# SCH_mechakey_2023-10-28.net
KiCad netlist of a schematic drawn in EasyEDA
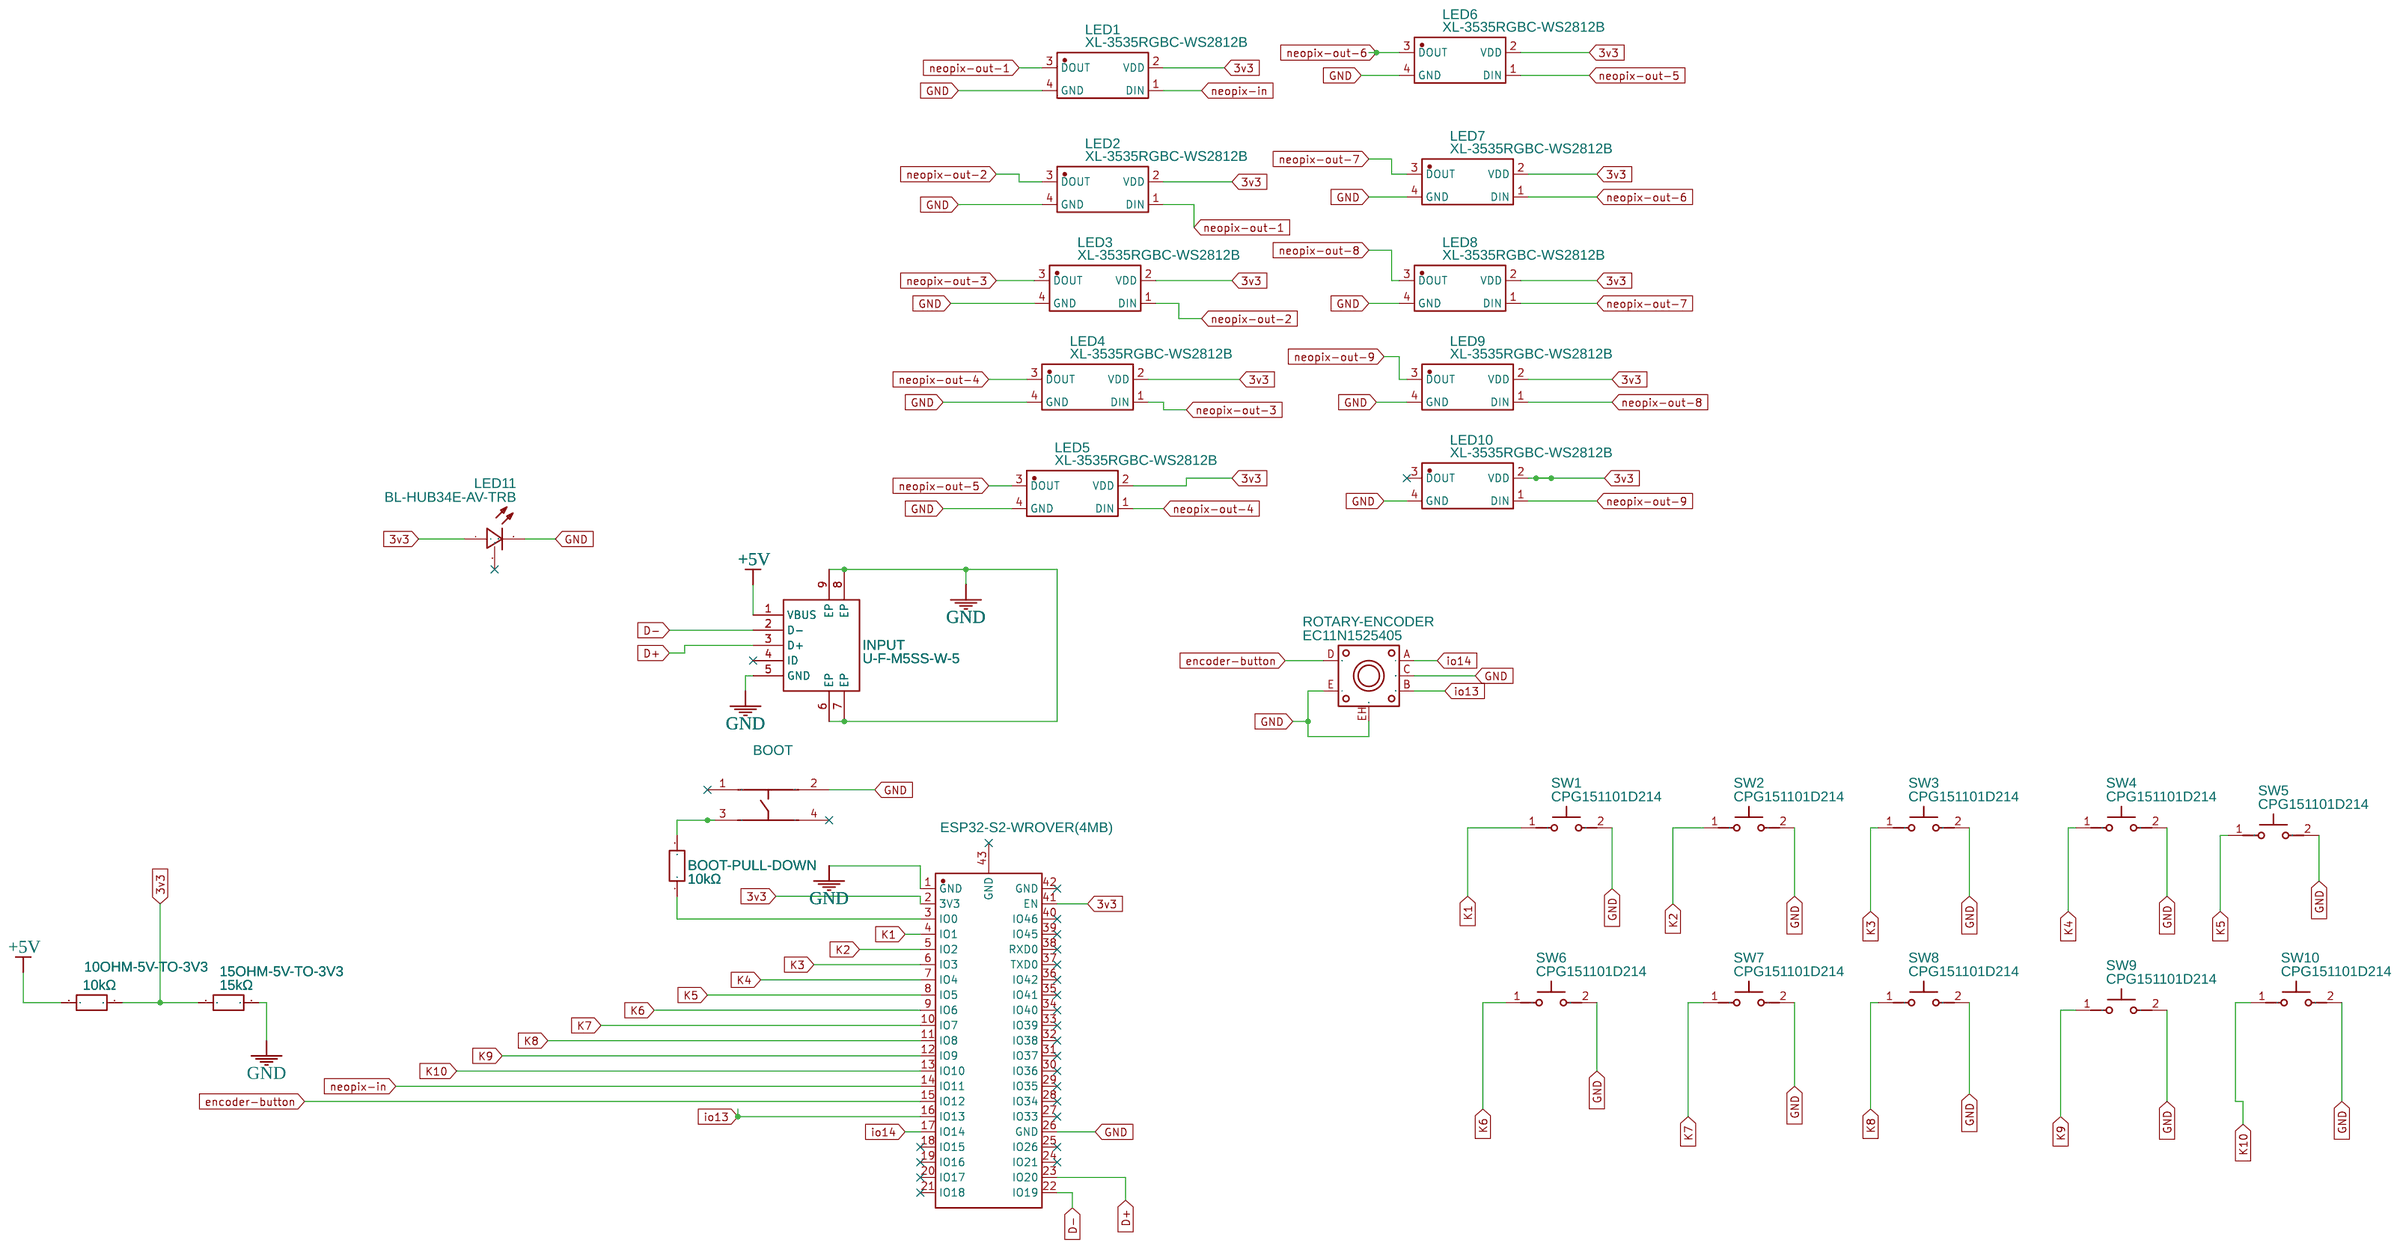
[diagram p0: schematic sheet]

(export (version "E")
  (design (tool "Eeschema 10.0.6"))
  (components
    (comp (ref "10OHM-5V-TO-3V3")
      (value "10kΩ")
      (fields (field (name "Manufacturer") "PANASONIC(松下)"))
      (libsource (lib "") (part "ERJUP3F1002V_1"))
    )
    (comp (ref "15OHM-5V-TO-3V3")
      (value "15kΩ")
      (fields (field (name "Manufacturer") "VO(翔胜)"))
      (libsource (lib "") (part "CR1/8W-15K±5%-OT26"))
    )
    (comp (ref "BOOT")
      (value "PTS810SJM250SMTRLFS")
      (fields (field (name "Manufacturer") "C&K"))
      (libsource (lib "") (part "PTS810SJM250SMTRLFS"))
    )
    (comp (ref "BOOT-PULL-DOWN")
      (value "10kΩ")
      (fields (field (name "Manufacturer") "PANASONIC(松下)"))
      (libsource (lib "") (part "ERJUP3F1002V"))
    )
    (comp (ref "INPUT")
      (value "U-F-M5SS-W-5")
      (fields (field (name "Manufacturer") "韩国韩荣"))
      (libsource (lib "") (part "U-F-M5SS-W-5"))
    )
    (comp (ref "LED1")
      (value "XL-3535RGBC-WS2812B")
      (fields (field (name "Manufacturer") "XINGLIGHT(成兴光)"))
      (libsource (lib "") (part "XL-3535RGBC-WS2812B"))
    )
    (comp (ref "LED2")
      (value "XL-3535RGBC-WS2812B")
      (fields (field (name "Manufacturer") "XINGLIGHT(成兴光)"))
      (libsource (lib "") (part "XL-3535RGBC-WS2812B"))
    )
    (comp (ref "LED3")
      (value "XL-3535RGBC-WS2812B")
      (fields (field (name "Manufacturer") "XINGLIGHT(成兴光)"))
      (libsource (lib "") (part "XL-3535RGBC-WS2812B"))
    )
    (comp (ref "LED4")
      (value "XL-3535RGBC-WS2812B")
      (fields (field (name "Manufacturer") "XINGLIGHT(成兴光)"))
      (libsource (lib "") (part "XL-3535RGBC-WS2812B"))
    )
    (comp (ref "LED5")
      (value "XL-3535RGBC-WS2812B")
      (fields (field (name "Manufacturer") "XINGLIGHT(成兴光)"))
      (libsource (lib "") (part "XL-3535RGBC-WS2812B"))
    )
    (comp (ref "LED6")
      (value "XL-3535RGBC-WS2812B")
      (fields (field (name "Manufacturer") "XINGLIGHT(成兴光)"))
      (libsource (lib "") (part "XL-3535RGBC-WS2812B"))
    )
    (comp (ref "LED7")
      (value "XL-3535RGBC-WS2812B")
      (fields (field (name "Manufacturer") "XINGLIGHT(成兴光)"))
      (libsource (lib "") (part "XL-3535RGBC-WS2812B"))
    )
    (comp (ref "LED8")
      (value "XL-3535RGBC-WS2812B")
      (fields (field (name "Manufacturer") "XINGLIGHT(成兴光)"))
      (libsource (lib "") (part "XL-3535RGBC-WS2812B"))
    )
    (comp (ref "LED9")
      (value "XL-3535RGBC-WS2812B")
      (fields (field (name "Manufacturer") "XINGLIGHT(成兴光)"))
      (libsource (lib "") (part "XL-3535RGBC-WS2812B"))
    )
    (comp (ref "LED10")
      (value "XL-3535RGBC-WS2812B")
      (fields (field (name "Manufacturer") "XINGLIGHT(成兴光)"))
      (libsource (lib "") (part "XL-3535RGBC-WS2812B"))
    )
    (comp (ref "LED11")
      (value "BL-HUB34E-AV-TRB")
      (fields (field (name "Manufacturer") "BrtLed(佰鸿)"))
      (libsource (lib "") (part "BL-HUB34E-AV-TRB"))
    )
    (comp (ref "ROTARY-ENCODER")
      (value "EC11N1525405")
      (fields (field (name "Manufacturer") "ALPSALPINE(阿尔卑斯阿尔派)"))
      (libsource (lib "") (part "EC11N1525405"))
    )
    (comp (ref "SW1")
      (value "CPG151101D214")
      (fields (field (name "Manufacturer") "Kailh"))
      (libsource (lib "") (part "CPG151101D214"))
    )
    (comp (ref "SW2")
      (value "CPG151101D214")
      (fields (field (name "Manufacturer") "Kailh"))
      (libsource (lib "") (part "CPG151101D214"))
    )
    (comp (ref "SW3")
      (value "CPG151101D214")
      (fields (field (name "Manufacturer") "Kailh"))
      (libsource (lib "") (part "CPG151101D214"))
    )
    (comp (ref "SW4")
      (value "CPG151101D214")
      (fields (field (name "Manufacturer") "Kailh"))
      (libsource (lib "") (part "CPG151101D214"))
    )
    (comp (ref "SW5")
      (value "CPG151101D214")
      (fields (field (name "Manufacturer") "Kailh"))
      (libsource (lib "") (part "CPG151101D214"))
    )
    (comp (ref "SW6")
      (value "CPG151101D214")
      (fields (field (name "Manufacturer") "Kailh"))
      (libsource (lib "") (part "CPG151101D214"))
    )
    (comp (ref "SW7")
      (value "CPG151101D214")
      (fields (field (name "Manufacturer") "Kailh"))
      (libsource (lib "") (part "CPG151101D214"))
    )
    (comp (ref "SW8")
      (value "CPG151101D214")
      (fields (field (name "Manufacturer") "Kailh"))
      (libsource (lib "") (part "CPG151101D214"))
    )
    (comp (ref "SW9")
      (value "CPG151101D214")
      (fields (field (name "Manufacturer") "Kailh"))
      (libsource (lib "") (part "CPG151101D214"))
    )
    (comp (ref "SW10")
      (value "CPG151101D214")
      (fields (field (name "Manufacturer") "Kailh"))
      (libsource (lib "") (part "CPG151101D214"))
    )
    (comp (ref "U1")
      (value "ESP32-S2-WROVER(4MB)")
      (fields (field (name "Manufacturer") "ESPRESSIF(乐鑫)"))
      (libsource (lib "") (part "ESP32-S2-WROVER(4MB)"))
    )
  )
  (nets
    (net (code "1") (name "+5V") (class "Default")
      (node (ref "10OHM-5V-TO-3V3") (pin "1") (pinfunction "1_1") (pintype "unspecified"))
      (node (ref "INPUT") (pin "1") (pinfunction "VBUS_1") (pintype "unspecified"))
    )
    (net (code "2") (name "3v3") (class "Default")
      (node (ref "10OHM-5V-TO-3V3") (pin "2") (pinfunction "2_2") (pintype "unspecified"))
      (node (ref "15OHM-5V-TO-3V3") (pin "1") (pinfunction "1_1") (pintype "unspecified"))
      (node (ref "LED1") (pin "2") (pinfunction "VDD_2") (pintype "unspecified"))
      (node (ref "LED10") (pin "2") (pinfunction "VDD_2") (pintype "unspecified"))
      (node (ref "LED11") (pin "1") (pinfunction "A_1") (pintype "unspecified"))
      (node (ref "LED2") (pin "2") (pinfunction "VDD_2") (pintype "unspecified"))
      (node (ref "LED3") (pin "2") (pinfunction "VDD_2") (pintype "unspecified"))
      (node (ref "LED4") (pin "2") (pinfunction "VDD_2") (pintype "unspecified"))
      (node (ref "LED5") (pin "2") (pinfunction "VDD_2") (pintype "unspecified"))
      (node (ref "LED6") (pin "2") (pinfunction "VDD_2") (pintype "unspecified"))
      (node (ref "LED7") (pin "2") (pinfunction "VDD_2") (pintype "unspecified"))
      (node (ref "LED8") (pin "2") (pinfunction "VDD_2") (pintype "unspecified"))
      (node (ref "LED9") (pin "2") (pinfunction "VDD_2") (pintype "unspecified"))
      (node (ref "U1") (pin "2") (pinfunction "3V3_2") (pintype "unspecified"))
      (node (ref "U1") (pin "41") (pinfunction "EN_41") (pintype "unspecified"))
    )
    (net (code "3") (name "D+") (class "Default")
      (node (ref "INPUT") (pin "3") (pinfunction "D+_3") (pintype "unspecified"))
      (node (ref "U1") (pin "23") (pinfunction "IO20_23") (pintype "unspecified"))
    )
    (net (code "4") (name "D-") (class "Default")
      (node (ref "INPUT") (pin "2") (pinfunction "D-_2") (pintype "unspecified"))
      (node (ref "U1") (pin "22") (pinfunction "IO19_22") (pintype "unspecified"))
    )
    (net (code "5") (name "GND") (class "Default")
      (node (ref "15OHM-5V-TO-3V3") (pin "2") (pinfunction "2_2") (pintype "unspecified"))
      (node (ref "BOOT") (pin "2") (pinfunction "2_2") (pintype "unspecified"))
      (node (ref "INPUT") (pin "5") (pinfunction "GND_5") (pintype "unspecified"))
      (node (ref "INPUT") (pin "6") (pinfunction "EP_6") (pintype "unspecified"))
      (node (ref "INPUT") (pin "7") (pinfunction "EP_7") (pintype "unspecified"))
      (node (ref "INPUT") (pin "8") (pinfunction "EP_8") (pintype "unspecified"))
      (node (ref "INPUT") (pin "9") (pinfunction "EP_9") (pintype "unspecified"))
      (node (ref "LED1") (pin "4") (pinfunction "GND_4") (pintype "unspecified"))
      (node (ref "LED10") (pin "4") (pinfunction "GND_4") (pintype "unspecified"))
      (node (ref "LED11") (pin "2") (pinfunction "C_2") (pintype "unspecified"))
      (node (ref "LED2") (pin "4") (pinfunction "GND_4") (pintype "unspecified"))
      (node (ref "LED3") (pin "4") (pinfunction "GND_4") (pintype "unspecified"))
      (node (ref "LED4") (pin "4") (pinfunction "GND_4") (pintype "unspecified"))
      (node (ref "LED5") (pin "4") (pinfunction "GND_4") (pintype "unspecified"))
      (node (ref "LED6") (pin "4") (pinfunction "GND_4") (pintype "unspecified"))
      (node (ref "LED7") (pin "4") (pinfunction "GND_4") (pintype "unspecified"))
      (node (ref "LED8") (pin "4") (pinfunction "GND_4") (pintype "unspecified"))
      (node (ref "LED9") (pin "4") (pinfunction "GND_4") (pintype "unspecified"))
      (node (ref "ROTARY-ENCODER") (pin "C") (pinfunction "C_C") (pintype "unspecified"))
      (node (ref "ROTARY-ENCODER") (pin "E") (pinfunction "E_E") (pintype "unspecified"))
      (node (ref "ROTARY-ENCODER") (pin "EH") (pinfunction "EH_EH") (pintype "unspecified"))
      (node (ref "SW1") (pin "2") (pinfunction "2_2") (pintype "unspecified"))
      (node (ref "SW10") (pin "2") (pinfunction "2_2") (pintype "unspecified"))
      (node (ref "SW2") (pin "2") (pinfunction "2_2") (pintype "unspecified"))
      (node (ref "SW3") (pin "2") (pinfunction "2_2") (pintype "unspecified"))
      (node (ref "SW4") (pin "2") (pinfunction "2_2") (pintype "unspecified"))
      (node (ref "SW5") (pin "2") (pinfunction "2_2") (pintype "unspecified"))
      (node (ref "SW6") (pin "2") (pinfunction "2_2") (pintype "unspecified"))
      (node (ref "SW7") (pin "2") (pinfunction "2_2") (pintype "unspecified"))
      (node (ref "SW8") (pin "2") (pinfunction "2_2") (pintype "unspecified"))
      (node (ref "SW9") (pin "2") (pinfunction "2_2") (pintype "unspecified"))
      (node (ref "U1") (pin "1") (pinfunction "GND_1") (pintype "unspecified"))
      (node (ref "U1") (pin "26") (pinfunction "GND_26") (pintype "unspecified"))
    )
    (net (code "6") (name "K1") (class "Default")
      (node (ref "SW1") (pin "1") (pinfunction "1_1") (pintype "unspecified"))
      (node (ref "U1") (pin "4") (pinfunction "IO1_4") (pintype "unspecified"))
    )
    (net (code "7") (name "K2") (class "Default")
      (node (ref "SW2") (pin "1") (pinfunction "1_1") (pintype "unspecified"))
      (node (ref "U1") (pin "5") (pinfunction "IO2_5") (pintype "unspecified"))
    )
    (net (code "8") (name "K3") (class "Default")
      (node (ref "SW3") (pin "1") (pinfunction "1_1") (pintype "unspecified"))
      (node (ref "U1") (pin "6") (pinfunction "IO3_6") (pintype "unspecified"))
    )
    (net (code "9") (name "K4") (class "Default")
      (node (ref "SW4") (pin "1") (pinfunction "1_1") (pintype "unspecified"))
      (node (ref "U1") (pin "7") (pinfunction "IO4_7") (pintype "unspecified"))
    )
    (net (code "10") (name "K5") (class "Default")
      (node (ref "SW5") (pin "1") (pinfunction "1_1") (pintype "unspecified"))
      (node (ref "U1") (pin "8") (pinfunction "IO5_8") (pintype "unspecified"))
    )
    (net (code "11") (name "K6") (class "Default")
      (node (ref "SW6") (pin "1") (pinfunction "1_1") (pintype "unspecified"))
      (node (ref "U1") (pin "9") (pinfunction "IO6_9") (pintype "unspecified"))
    )
    (net (code "12") (name "K7") (class "Default")
      (node (ref "SW7") (pin "1") (pinfunction "1_1") (pintype "unspecified"))
      (node (ref "U1") (pin "10") (pinfunction "IO7_10") (pintype "unspecified"))
    )
    (net (code "13") (name "K8") (class "Default")
      (node (ref "SW8") (pin "1") (pinfunction "1_1") (pintype "unspecified"))
      (node (ref "U1") (pin "11") (pinfunction "IO8_11") (pintype "unspecified"))
    )
    (net (code "14") (name "K9") (class "Default")
      (node (ref "SW9") (pin "1") (pinfunction "1_1") (pintype "unspecified"))
      (node (ref "U1") (pin "12") (pinfunction "IO9_12") (pintype "unspecified"))
    )
    (net (code "15") (name "K10") (class "Default")
      (node (ref "SW10") (pin "1") (pinfunction "1_1") (pintype "unspecified"))
      (node (ref "U1") (pin "13") (pinfunction "IO10_13") (pintype "unspecified"))
    )
    (net (code "16") (name "Net-(BOOT-PULL-DOWN-Pad2)") (class "Default")
      (node (ref "BOOT") (pin "3") (pinfunction "3_3") (pintype "unspecified"))
      (node (ref "BOOT-PULL-DOWN") (pin "2") (pinfunction "2_2") (pintype "unspecified"))
    )
    (net (code "17") (name "Net-(U1-IO0)") (class "Default")
      (node (ref "BOOT-PULL-DOWN") (pin "1") (pinfunction "1_1") (pintype "unspecified"))
      (node (ref "U1") (pin "3") (pinfunction "IO0_3") (pintype "unspecified"))
    )
    (net (code "18") (name "encoder-button") (class "Default")
      (node (ref "ROTARY-ENCODER") (pin "D") (pinfunction "D_D") (pintype "unspecified"))
      (node (ref "U1") (pin "15") (pinfunction "IO12_15") (pintype "unspecified"))
    )
    (net (code "19") (name "io13") (class "Default")
      (node (ref "ROTARY-ENCODER") (pin "B") (pinfunction "B_B") (pintype "unspecified"))
      (node (ref "U1") (pin "16") (pinfunction "IO13_16") (pintype "unspecified"))
    )
    (net (code "20") (name "io14") (class "Default")
      (node (ref "ROTARY-ENCODER") (pin "A") (pinfunction "A_A") (pintype "unspecified"))
      (node (ref "U1") (pin "17") (pinfunction "IO14_17") (pintype "unspecified"))
    )
    (net (code "21") (name "neopix-in") (class "Default")
      (node (ref "LED1") (pin "1") (pinfunction "DIN_1") (pintype "unspecified"))
      (node (ref "U1") (pin "14") (pinfunction "IO11_14") (pintype "unspecified"))
    )
    (net (code "22") (name "neopix-out-1") (class "Default")
      (node (ref "LED1") (pin "3") (pinfunction "DOUT_3") (pintype "unspecified"))
      (node (ref "LED2") (pin "1") (pinfunction "DIN_1") (pintype "unspecified"))
    )
    (net (code "23") (name "neopix-out-2") (class "Default")
      (node (ref "LED2") (pin "3") (pinfunction "DOUT_3") (pintype "unspecified"))
      (node (ref "LED3") (pin "1") (pinfunction "DIN_1") (pintype "unspecified"))
    )
    (net (code "24") (name "neopix-out-3") (class "Default")
      (node (ref "LED3") (pin "3") (pinfunction "DOUT_3") (pintype "unspecified"))
      (node (ref "LED4") (pin "1") (pinfunction "DIN_1") (pintype "unspecified"))
    )
    (net (code "25") (name "neopix-out-4") (class "Default")
      (node (ref "LED4") (pin "3") (pinfunction "DOUT_3") (pintype "unspecified"))
      (node (ref "LED5") (pin "1") (pinfunction "DIN_1") (pintype "unspecified"))
    )
    (net (code "26") (name "neopix-out-5") (class "Default")
      (node (ref "LED5") (pin "3") (pinfunction "DOUT_3") (pintype "unspecified"))
      (node (ref "LED6") (pin "1") (pinfunction "DIN_1") (pintype "unspecified"))
    )
    (net (code "27") (name "neopix-out-6") (class "Default")
      (node (ref "LED6") (pin "3") (pinfunction "DOUT_3") (pintype "unspecified"))
      (node (ref "LED7") (pin "1") (pinfunction "DIN_1") (pintype "unspecified"))
    )
    (net (code "28") (name "neopix-out-7") (class "Default")
      (node (ref "LED7") (pin "3") (pinfunction "DOUT_3") (pintype "unspecified"))
      (node (ref "LED8") (pin "1") (pinfunction "DIN_1") (pintype "unspecified"))
    )
    (net (code "29") (name "neopix-out-8") (class "Default")
      (node (ref "LED8") (pin "3") (pinfunction "DOUT_3") (pintype "unspecified"))
      (node (ref "LED9") (pin "1") (pinfunction "DIN_1") (pintype "unspecified"))
    )
    (net (code "30") (name "neopix-out-9") (class "Default")
      (node (ref "LED10") (pin "1") (pinfunction "DIN_1") (pintype "unspecified"))
      (node (ref "LED9") (pin "3") (pinfunction "DOUT_3") (pintype "unspecified"))
    )
    (net (code "31") (name "unconnected-(BOOT-Pad1)") (class "Default")
      (node (ref "BOOT") (pin "1") (pinfunction "1_1") (pintype "unspecified+no_connect"))
    )
    (net (code "32") (name "unconnected-(BOOT-Pad4)") (class "Default")
      (node (ref "BOOT") (pin "4") (pinfunction "4_4") (pintype "unspecified+no_connect"))
    )
    (net (code "33") (name "unconnected-(INPUT-ID-Pad4)") (class "Default")
      (node (ref "INPUT") (pin "4") (pinfunction "ID_4") (pintype "unspecified+no_connect"))
    )
    (net (code "34") (name "unconnected-(LED10-DOUT-Pad3)") (class "Default")
      (node (ref "LED10") (pin "3") (pinfunction "DOUT_3") (pintype "unspecified+no_connect"))
    )
    (net (code "35") (name "unconnected-(LED11-Pad3)") (class "Default")
      (node (ref "LED11") (pin "3") (pinfunction "3_3") (pintype "unspecified+no_connect"))
    )
    (net (code "36") (name "unconnected-(U1-GND-Pad42)") (class "Default")
      (node (ref "U1") (pin "42") (pinfunction "GND_42") (pintype "unspecified+no_connect"))
    )
    (net (code "37") (name "unconnected-(U1-GND-Pad43)") (class "Default")
      (node (ref "U1") (pin "43") (pinfunction "GND_43") (pintype "unspecified+no_connect"))
    )
    (net (code "38") (name "unconnected-(U1-IO15-Pad18)") (class "Default")
      (node (ref "U1") (pin "18") (pinfunction "IO15_18") (pintype "unspecified+no_connect"))
    )
    (net (code "39") (name "unconnected-(U1-IO16-Pad19)") (class "Default")
      (node (ref "U1") (pin "19") (pinfunction "IO16_19") (pintype "unspecified+no_connect"))
    )
    (net (code "40") (name "unconnected-(U1-IO17-Pad20)") (class "Default")
      (node (ref "U1") (pin "20") (pinfunction "IO17_20") (pintype "unspecified+no_connect"))
    )
    (net (code "41") (name "unconnected-(U1-IO18-Pad21)") (class "Default")
      (node (ref "U1") (pin "21") (pinfunction "IO18_21") (pintype "unspecified+no_connect"))
    )
    (net (code "42") (name "unconnected-(U1-IO21-Pad24)") (class "Default")
      (node (ref "U1") (pin "24") (pinfunction "IO21_24") (pintype "unspecified+no_connect"))
    )
    (net (code "43") (name "unconnected-(U1-IO26-Pad25)") (class "Default")
      (node (ref "U1") (pin "25") (pinfunction "IO26_25") (pintype "unspecified+no_connect"))
    )
    (net (code "44") (name "unconnected-(U1-IO33-Pad27)") (class "Default")
      (node (ref "U1") (pin "27") (pinfunction "IO33_27") (pintype "unspecified+no_connect"))
    )
    (net (code "45") (name "unconnected-(U1-IO34-Pad28)") (class "Default")
      (node (ref "U1") (pin "28") (pinfunction "IO34_28") (pintype "unspecified+no_connect"))
    )
    (net (code "46") (name "unconnected-(U1-IO35-Pad29)") (class "Default")
      (node (ref "U1") (pin "29") (pinfunction "IO35_29") (pintype "unspecified+no_connect"))
    )
    (net (code "47") (name "unconnected-(U1-IO36-Pad30)") (class "Default")
      (node (ref "U1") (pin "30") (pinfunction "IO36_30") (pintype "unspecified+no_connect"))
    )
    (net (code "48") (name "unconnected-(U1-IO37-Pad31)") (class "Default")
      (node (ref "U1") (pin "31") (pinfunction "IO37_31") (pintype "unspecified+no_connect"))
    )
    (net (code "49") (name "unconnected-(U1-IO38-Pad32)") (class "Default")
      (node (ref "U1") (pin "32") (pinfunction "IO38_32") (pintype "unspecified+no_connect"))
    )
    (net (code "50") (name "unconnected-(U1-IO39-Pad33)") (class "Default")
      (node (ref "U1") (pin "33") (pinfunction "IO39_33") (pintype "unspecified+no_connect"))
    )
    (net (code "51") (name "unconnected-(U1-IO40-Pad34)") (class "Default")
      (node (ref "U1") (pin "34") (pinfunction "IO40_34") (pintype "unspecified+no_connect"))
    )
    (net (code "52") (name "unconnected-(U1-IO41-Pad35)") (class "Default")
      (node (ref "U1") (pin "35") (pinfunction "IO41_35") (pintype "unspecified+no_connect"))
    )
    (net (code "53") (name "unconnected-(U1-IO42-Pad36)") (class "Default")
      (node (ref "U1") (pin "36") (pinfunction "IO42_36") (pintype "unspecified+no_connect"))
    )
    (net (code "54") (name "unconnected-(U1-IO45-Pad39)") (class "Default")
      (node (ref "U1") (pin "39") (pinfunction "IO45_39") (pintype "unspecified+no_connect"))
    )
    (net (code "55") (name "unconnected-(U1-IO46-Pad40)") (class "Default")
      (node (ref "U1") (pin "40") (pinfunction "IO46_40") (pintype "unspecified+no_connect"))
    )
    (net (code "56") (name "unconnected-(U1-RXD0-Pad38)") (class "Default")
      (node (ref "U1") (pin "38") (pinfunction "RXD0_38") (pintype "unspecified+no_connect"))
    )
    (net (code "57") (name "unconnected-(U1-TXD0-Pad37)") (class "Default")
      (node (ref "U1") (pin "37") (pinfunction "TXD0_37") (pintype "unspecified+no_connect"))
    )
  )
)
